# led.net
KiCad netlist of a schematic drawn in EAGLE
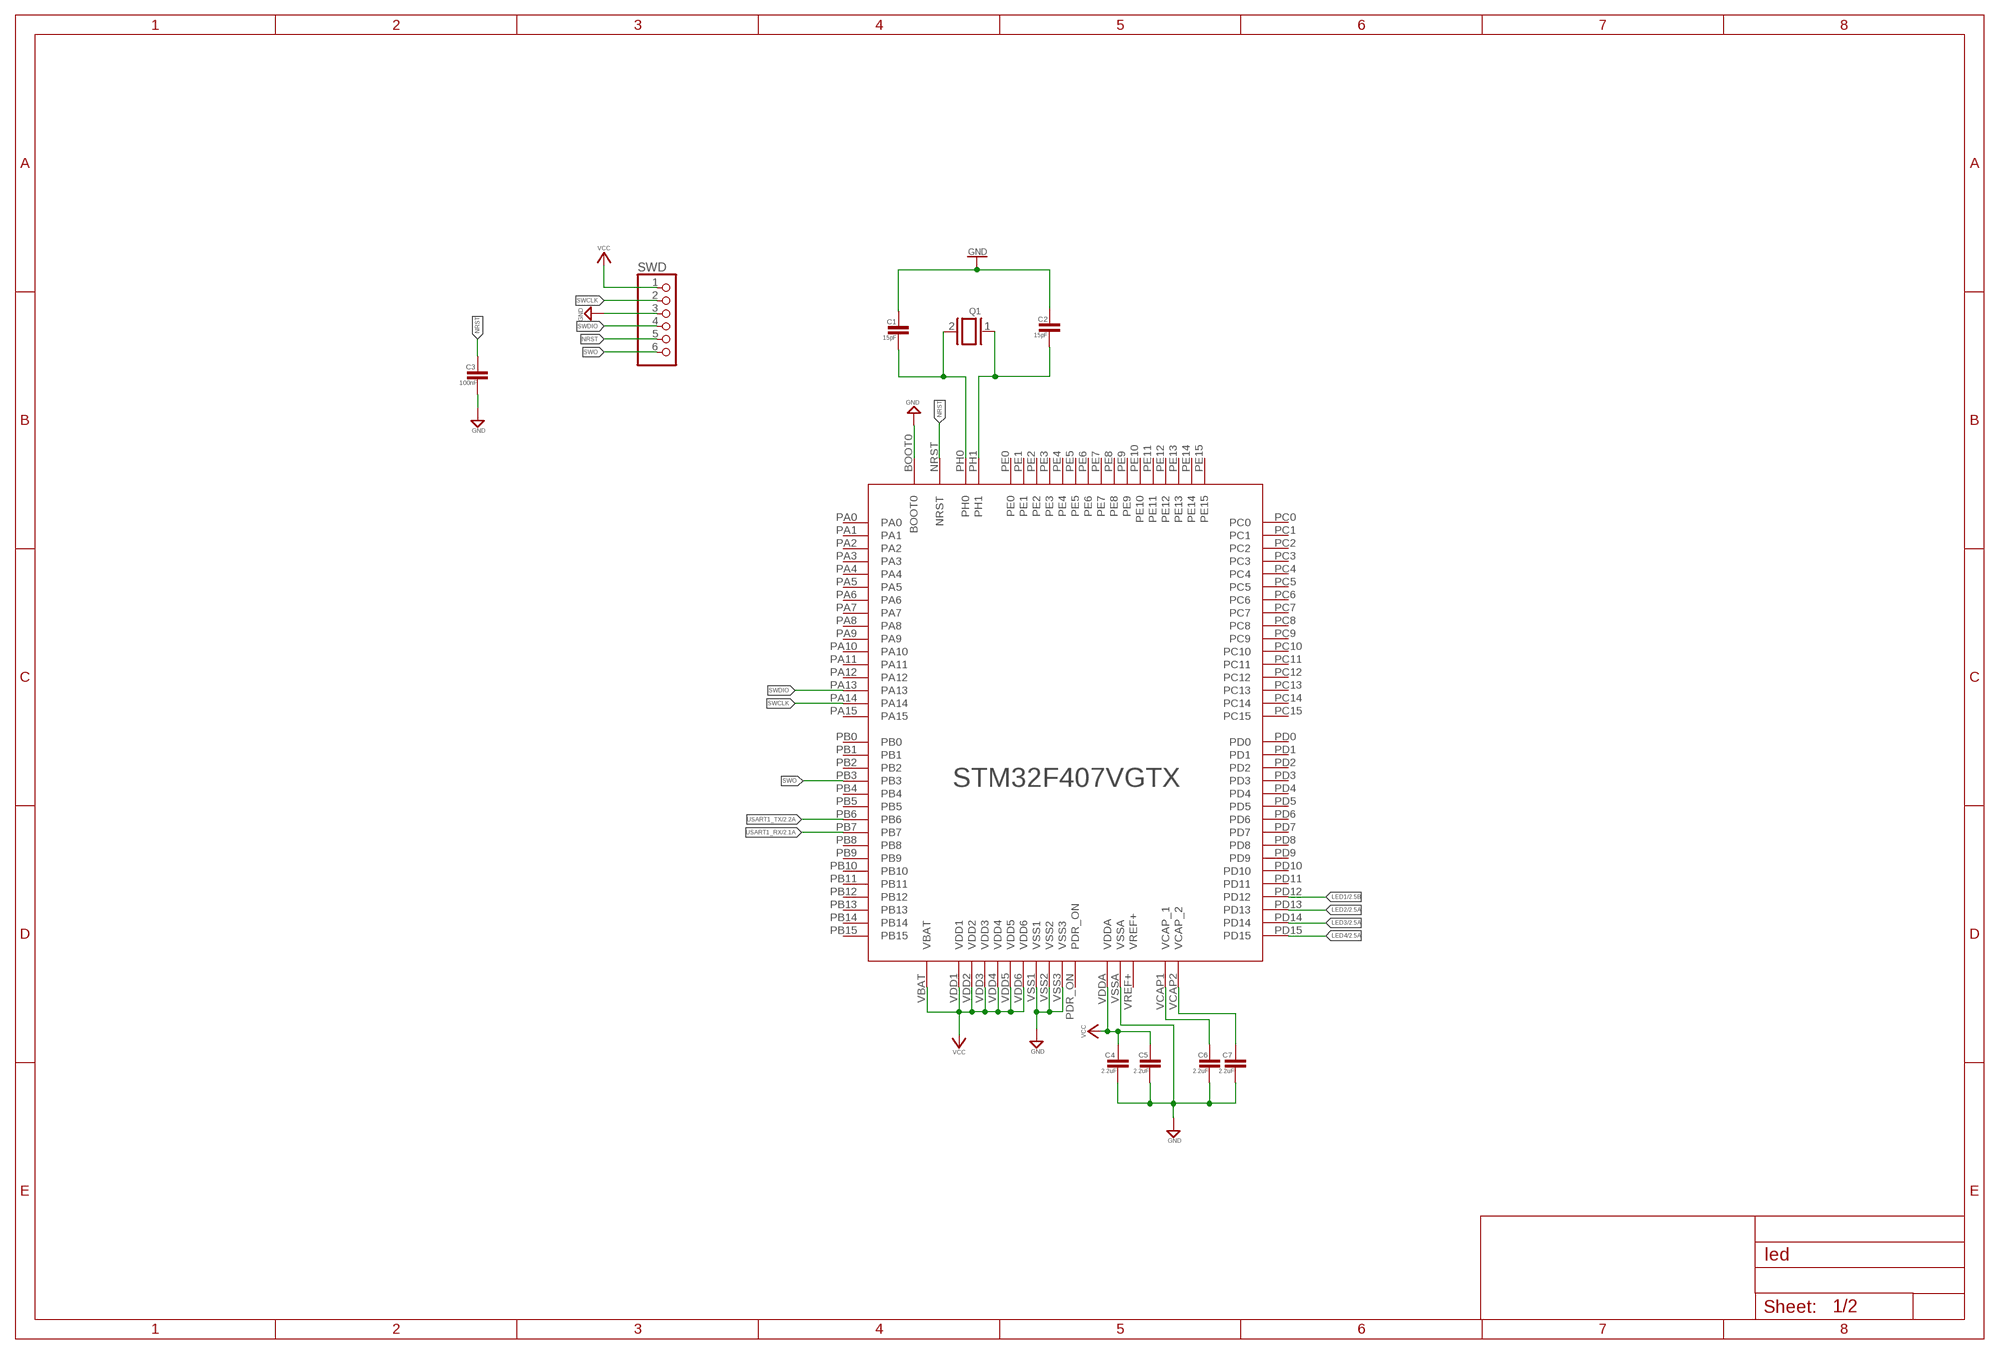
[diagram p0: schematic, sheet 1]
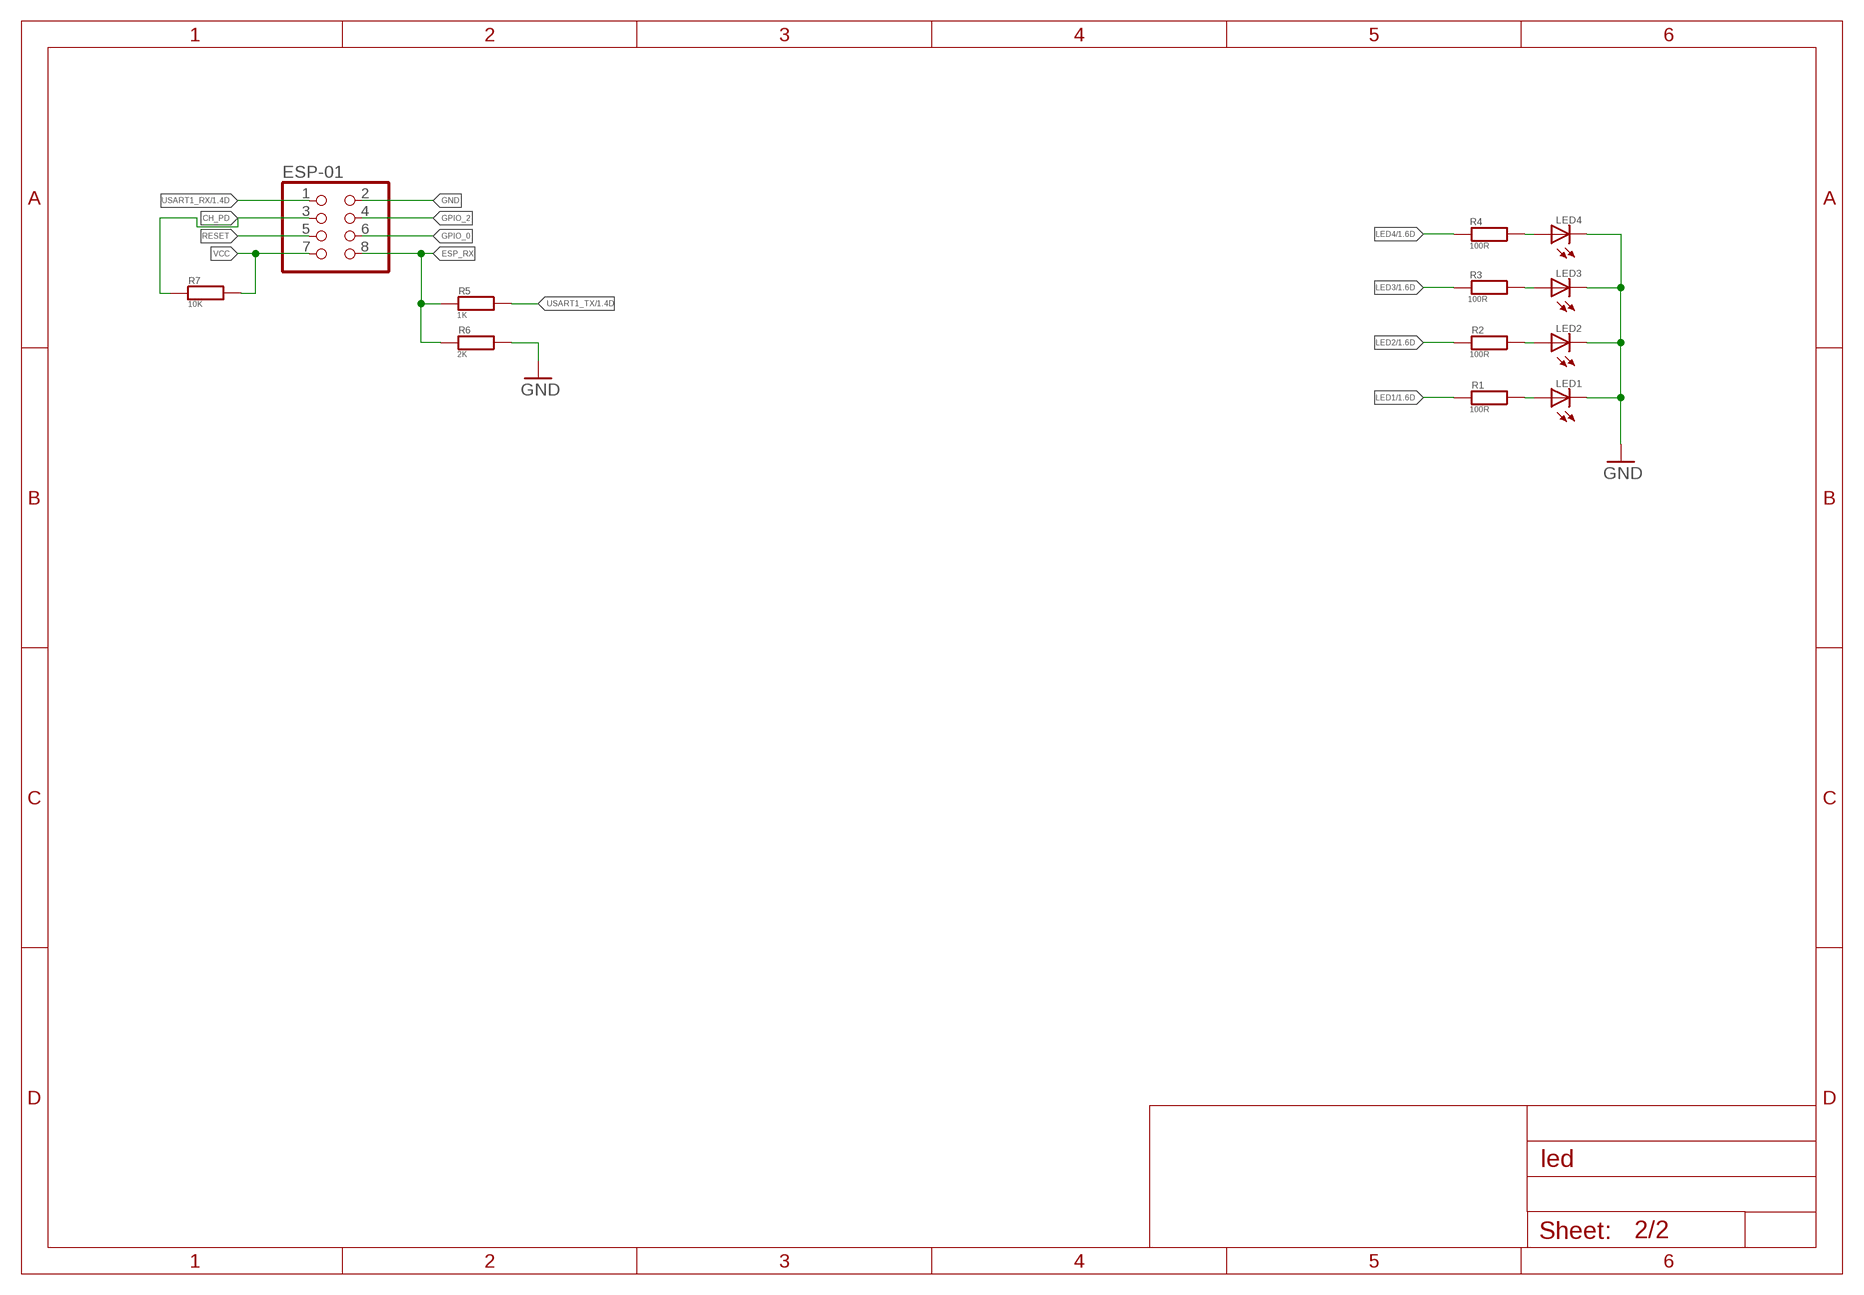
[diagram p1: schematic, sheet 2]

(export (version "E")
  (design (tool "Eeschema 10.0.6"))
  (components
    (comp (ref "C1")
      (value "15pF")
      (footprint "eagle-import:C0603")
      (libsource (lib "eagle-import") (part "C-EUC0603"))
    )
    (comp (ref "C2")
      (value "15pF")
      (footprint "eagle-import:C0603")
      (libsource (lib "eagle-import") (part "C-EUC0603"))
    )
    (comp (ref "C3")
      (value "100nF")
      (footprint "eagle-import:C0603")
      (libsource (lib "eagle-import") (part "C-EUC0603"))
    )
    (comp (ref "C4")
      (value "2.2uF")
      (footprint "eagle-import:C0603")
      (libsource (lib "eagle-import") (part "C-EUC0603"))
    )
    (comp (ref "C5")
      (value "2.2uF")
      (footprint "eagle-import:C0603")
      (libsource (lib "eagle-import") (part "C-EUC0603"))
    )
    (comp (ref "C6")
      (value "2.2uF")
      (footprint "eagle-import:C0603")
      (libsource (lib "eagle-import") (part "C-EUC0603"))
    )
    (comp (ref "C7")
      (value "2.2uF")
      (footprint "eagle-import:C0603")
      (libsource (lib "eagle-import") (part "C-EUC0603"))
    )
    (comp (ref "IC1")
      (value "STM32F407VGTx")
      (footprint "eagle-import:LQFP100")
      (libsource (lib "eagle-import") (part "STM32F4V_100PIN_GENERIC"))
    )
    (comp (ref "Q1")
      (value "XTAL/S")
      (footprint "eagle-import:QS")
      (libsource (lib "eagle-import") (part "XTAL/S"))
    )
    (comp (ref "SWD")
      (value "PINHD-1X6CB")
      (footprint "eagle-import:1X06-CLEANBIG")
      (libsource (lib "eagle-import") (part "PINHD-1X6CB"))
    )
    (comp (ref "ESP-01")
      (value "PINHD-2X4")
      (footprint "eagle-import:2X04")
      (libsource (lib "eagle-import") (part "PINHD-2X4"))
    )
    (comp (ref "LED1")
      (value "LEDCHIPLED_1206")
      (footprint "eagle-import:CHIPLED_1206")
      (libsource (lib "eagle-import") (part "LEDCHIPLED_1206"))
    )
    (comp (ref "LED2")
      (value "LEDCHIPLED_1206")
      (footprint "eagle-import:CHIPLED_1206")
      (libsource (lib "eagle-import") (part "LEDCHIPLED_1206"))
    )
    (comp (ref "LED3")
      (value "LEDCHIPLED_1206")
      (footprint "eagle-import:CHIPLED_1206")
      (libsource (lib "eagle-import") (part "LEDCHIPLED_1206"))
    )
    (comp (ref "LED4")
      (value "LEDCHIPLED_1206")
      (footprint "eagle-import:CHIPLED_1206")
      (libsource (lib "eagle-import") (part "LEDCHIPLED_1206"))
    )
    (comp (ref "R1")
      (value "100R")
      (footprint "eagle-import:R0603")
      (libsource (lib "eagle-import") (part "R-EU_R0603"))
    )
    (comp (ref "R2")
      (value "100R")
      (footprint "eagle-import:R0603")
      (libsource (lib "eagle-import") (part "R-EU_R0603"))
    )
    (comp (ref "R3")
      (value "100R")
      (footprint "eagle-import:R0603")
      (libsource (lib "eagle-import") (part "R-EU_R0603"))
    )
    (comp (ref "R4")
      (value "100R")
      (footprint "eagle-import:R0603")
      (libsource (lib "eagle-import") (part "R-EU_R0603"))
    )
    (comp (ref "R5")
      (value "1K")
      (footprint "eagle-import:R0603")
      (libsource (lib "eagle-import") (part "R-EU_R0603"))
    )
    (comp (ref "R6")
      (value "2K")
      (footprint "eagle-import:R0603")
      (libsource (lib "eagle-import") (part "R-EU_R0603"))
    )
    (comp (ref "R7")
      (value "10K")
      (footprint "eagle-import:R0603")
      (libsource (lib "eagle-import") (part "R-EU_R0603"))
    )
  )
  (nets
    (net (code "1") (name "CH_PD") (class "Default")
      (node (ref "ESP-01") (pin "3") (pinfunction "3_3") (pintype "passive"))
      (node (ref "R7") (pin "1") (pinfunction "1_1") (pintype "passive"))
    )
    (net (code "2") (name "ESP_RX") (class "Default")
      (node (ref "ESP-01") (pin "8") (pinfunction "8_8") (pintype "passive"))
      (node (ref "R5") (pin "2") (pinfunction "2_2") (pintype "passive"))
      (node (ref "R6") (pin "2") (pinfunction "2_2") (pintype "passive"))
    )
    (net (code "3") (name "GND") (class "Default")
      (node (ref "C1") (pin "1") (pinfunction "1_1") (pintype "passive"))
      (node (ref "C2") (pin "1") (pinfunction "1_1") (pintype "passive"))
      (node (ref "C3") (pin "2") (pinfunction "2_2") (pintype "passive"))
      (node (ref "C4") (pin "2") (pinfunction "2_2") (pintype "passive"))
      (node (ref "C5") (pin "2") (pinfunction "2_2") (pintype "passive"))
      (node (ref "C6") (pin "2") (pinfunction "2_2") (pintype "passive"))
      (node (ref "C7") (pin "2") (pinfunction "2_2") (pintype "passive"))
      (node (ref "ESP-01") (pin "2") (pinfunction "2_2") (pintype "passive"))
      (node (ref "IC1") (pin "BOOT0") (pinfunction "BOOT0_BOOT0") (pintype "bidirectional"))
      (node (ref "IC1") (pin "VSS1") (pinfunction "VSS1_VSS1") (pintype "bidirectional"))
      (node (ref "IC1") (pin "VSS2") (pinfunction "VSS2_VSS2") (pintype "bidirectional"))
      (node (ref "IC1") (pin "VSS3") (pinfunction "VSS3_VSS3") (pintype "bidirectional"))
      (node (ref "IC1") (pin "VSSA") (pinfunction "VSSA_VSSA") (pintype "bidirectional"))
      (node (ref "LED1") (pin "C") (pinfunction "C_C") (pintype "passive"))
      (node (ref "LED2") (pin "C") (pinfunction "C_C") (pintype "passive"))
      (node (ref "LED3") (pin "C") (pinfunction "C_C") (pintype "passive"))
      (node (ref "LED4") (pin "C") (pinfunction "C_C") (pintype "passive"))
      (node (ref "R6") (pin "1") (pinfunction "1_1") (pintype "passive"))
      (node (ref "SWD") (pin "3") (pinfunction "3_3") (pintype "passive"))
    )
    (net (code "4") (name "GPIO_0") (class "Default")
      (node (ref "ESP-01") (pin "6") (pinfunction "6_6") (pintype "passive"))
    )
    (net (code "5") (name "GPIO_2") (class "Default")
      (node (ref "ESP-01") (pin "4") (pinfunction "4_4") (pintype "passive"))
    )
    (net (code "6") (name "LED1") (class "Default")
      (node (ref "IC1") (pin "PD12") (pinfunction "PD12_PD12") (pintype "bidirectional"))
      (node (ref "R1") (pin "2") (pinfunction "2_2") (pintype "passive"))
    )
    (net (code "7") (name "LED2") (class "Default")
      (node (ref "IC1") (pin "PD13") (pinfunction "PD13_PD13") (pintype "bidirectional"))
      (node (ref "R2") (pin "2") (pinfunction "2_2") (pintype "passive"))
    )
    (net (code "8") (name "LED3") (class "Default")
      (node (ref "IC1") (pin "PD14") (pinfunction "PD14_PD14") (pintype "bidirectional"))
      (node (ref "R3") (pin "2") (pinfunction "2_2") (pintype "passive"))
    )
    (net (code "9") (name "LED4") (class "Default")
      (node (ref "IC1") (pin "PD15") (pinfunction "PD15_PD15") (pintype "bidirectional"))
      (node (ref "R4") (pin "2") (pinfunction "2_2") (pintype "passive"))
    )
    (net (code "10") (name "NRST") (class "Default")
      (node (ref "C3") (pin "1") (pinfunction "1_1") (pintype "passive"))
      (node (ref "IC1") (pin "NRST") (pinfunction "NRST_NRST") (pintype "bidirectional"))
      (node (ref "SWD") (pin "5") (pinfunction "5_5") (pintype "passive"))
    )
    (net (code "11") (name "Net-(C1-Pad2)") (class "Default")
      (node (ref "C1") (pin "2") (pinfunction "2_2") (pintype "passive"))
      (node (ref "IC1") (pin "PH0") (pinfunction "PH0_PH0") (pintype "bidirectional"))
      (node (ref "Q1") (pin "2") (pinfunction "2_2") (pintype "passive"))
    )
    (net (code "12") (name "Net-(C2-Pad2)") (class "Default")
      (node (ref "C2") (pin "2") (pinfunction "2_2") (pintype "passive"))
      (node (ref "IC1") (pin "PH1") (pinfunction "PH1_PH1") (pintype "bidirectional"))
      (node (ref "Q1") (pin "1") (pinfunction "1_1") (pintype "passive"))
    )
    (net (code "13") (name "Net-(IC1-VCAP_1)") (class "Default")
      (node (ref "C6") (pin "1") (pinfunction "1_1") (pintype "passive"))
      (node (ref "IC1") (pin "VCAP1") (pinfunction "VCAP_1_VCAP1") (pintype "bidirectional"))
    )
    (net (code "14") (name "Net-(IC1-VCAP_2)") (class "Default")
      (node (ref "C7") (pin "1") (pinfunction "1_1") (pintype "passive"))
      (node (ref "IC1") (pin "VCAP2") (pinfunction "VCAP_2_VCAP2") (pintype "bidirectional"))
    )
    (net (code "15") (name "Net-(LED1-PadA)") (class "Default")
      (node (ref "LED1") (pin "A") (pinfunction "A_A") (pintype "passive"))
      (node (ref "R1") (pin "1") (pinfunction "1_1") (pintype "passive"))
    )
    (net (code "16") (name "Net-(LED2-PadA)") (class "Default")
      (node (ref "LED2") (pin "A") (pinfunction "A_A") (pintype "passive"))
      (node (ref "R2") (pin "1") (pinfunction "1_1") (pintype "passive"))
    )
    (net (code "17") (name "Net-(LED3-PadA)") (class "Default")
      (node (ref "LED3") (pin "A") (pinfunction "A_A") (pintype "passive"))
      (node (ref "R3") (pin "1") (pinfunction "1_1") (pintype "passive"))
    )
    (net (code "18") (name "Net-(LED4-PadA)") (class "Default")
      (node (ref "LED4") (pin "A") (pinfunction "A_A") (pintype "passive"))
      (node (ref "R4") (pin "1") (pinfunction "1_1") (pintype "passive"))
    )
    (net (code "19") (name "RESET") (class "Default")
      (node (ref "ESP-01") (pin "5") (pinfunction "5_5") (pintype "passive"))
    )
    (net (code "20") (name "SWCLK") (class "Default")
      (node (ref "IC1") (pin "PA14") (pinfunction "PA14_PA14") (pintype "bidirectional"))
      (node (ref "SWD") (pin "2") (pinfunction "2_2") (pintype "passive"))
    )
    (net (code "21") (name "SWDIO") (class "Default")
      (node (ref "IC1") (pin "PA13") (pinfunction "PA13_PA13") (pintype "bidirectional"))
      (node (ref "SWD") (pin "4") (pinfunction "4_4") (pintype "passive"))
    )
    (net (code "22") (name "SWO") (class "Default")
      (node (ref "IC1") (pin "PB3") (pinfunction "PB3_PB3") (pintype "bidirectional"))
      (node (ref "SWD") (pin "6") (pinfunction "6_6") (pintype "passive"))
    )
    (net (code "23") (name "USART1_RX") (class "Default")
      (node (ref "ESP-01") (pin "1") (pinfunction "1_1") (pintype "passive"))
      (node (ref "IC1") (pin "PB7") (pinfunction "PB7_PB7") (pintype "bidirectional"))
    )
    (net (code "24") (name "USART1_TX") (class "Default")
      (node (ref "IC1") (pin "PB6") (pinfunction "PB6_PB6") (pintype "bidirectional"))
      (node (ref "R5") (pin "1") (pinfunction "1_1") (pintype "passive"))
    )
    (net (code "25") (name "VCC") (class "Default")
      (node (ref "C4") (pin "1") (pinfunction "1_1") (pintype "passive"))
      (node (ref "C5") (pin "1") (pinfunction "1_1") (pintype "passive"))
      (node (ref "ESP-01") (pin "7") (pinfunction "7_7") (pintype "passive"))
      (node (ref "IC1") (pin "VBAT") (pinfunction "VBAT_VBAT") (pintype "bidirectional"))
      (node (ref "IC1") (pin "VDD1") (pinfunction "VDD1_VDD1") (pintype "bidirectional"))
      (node (ref "IC1") (pin "VDD2") (pinfunction "VDD2_VDD2") (pintype "bidirectional"))
      (node (ref "IC1") (pin "VDD3") (pinfunction "VDD3_VDD3") (pintype "bidirectional"))
      (node (ref "IC1") (pin "VDD4") (pinfunction "VDD4_VDD4") (pintype "bidirectional"))
      (node (ref "IC1") (pin "VDD5") (pinfunction "VDD5_VDD5") (pintype "bidirectional"))
      (node (ref "IC1") (pin "VDD6") (pinfunction "VDD6_VDD6") (pintype "bidirectional"))
      (node (ref "IC1") (pin "VDDA") (pinfunction "VDDA_VDDA") (pintype "bidirectional"))
      (node (ref "R7") (pin "2") (pinfunction "2_2") (pintype "passive"))
      (node (ref "SWD") (pin "1") (pinfunction "1_1") (pintype "passive"))
    )
    (net (code "26") (name "unconnected-(IC1-PadPA0)") (class "Default")
      (node (ref "IC1") (pin "PA0") (pinfunction "PA0_PA0") (pintype "bidirectional"))
    )
    (net (code "27") (name "unconnected-(IC1-PadPA1)") (class "Default")
      (node (ref "IC1") (pin "PA1") (pinfunction "PA1_PA1") (pintype "bidirectional"))
    )
    (net (code "28") (name "unconnected-(IC1-PadPA2)") (class "Default")
      (node (ref "IC1") (pin "PA2") (pinfunction "PA2_PA2") (pintype "bidirectional"))
    )
    (net (code "29") (name "unconnected-(IC1-PadPA3)") (class "Default")
      (node (ref "IC1") (pin "PA3") (pinfunction "PA3_PA3") (pintype "bidirectional"))
    )
    (net (code "30") (name "unconnected-(IC1-PadPA4)") (class "Default")
      (node (ref "IC1") (pin "PA4") (pinfunction "PA4_PA4") (pintype "bidirectional"))
    )
    (net (code "31") (name "unconnected-(IC1-PadPA5)") (class "Default")
      (node (ref "IC1") (pin "PA5") (pinfunction "PA5_PA5") (pintype "bidirectional"))
    )
    (net (code "32") (name "unconnected-(IC1-PadPA6)") (class "Default")
      (node (ref "IC1") (pin "PA6") (pinfunction "PA6_PA6") (pintype "bidirectional"))
    )
    (net (code "33") (name "unconnected-(IC1-PadPA7)") (class "Default")
      (node (ref "IC1") (pin "PA7") (pinfunction "PA7_PA7") (pintype "bidirectional"))
    )
    (net (code "34") (name "unconnected-(IC1-PadPA8)") (class "Default")
      (node (ref "IC1") (pin "PA8") (pinfunction "PA8_PA8") (pintype "bidirectional"))
    )
    (net (code "35") (name "unconnected-(IC1-PadPA9)") (class "Default")
      (node (ref "IC1") (pin "PA9") (pinfunction "PA9_PA9") (pintype "bidirectional"))
    )
    (net (code "36") (name "unconnected-(IC1-PadPA10)") (class "Default")
      (node (ref "IC1") (pin "PA10") (pinfunction "PA10_PA10") (pintype "bidirectional"))
    )
    (net (code "37") (name "unconnected-(IC1-PadPA11)") (class "Default")
      (node (ref "IC1") (pin "PA11") (pinfunction "PA11_PA11") (pintype "bidirectional"))
    )
    (net (code "38") (name "unconnected-(IC1-PadPA12)") (class "Default")
      (node (ref "IC1") (pin "PA12") (pinfunction "PA12_PA12") (pintype "bidirectional"))
    )
    (net (code "39") (name "unconnected-(IC1-PadPA15)") (class "Default")
      (node (ref "IC1") (pin "PA15") (pinfunction "PA15_PA15") (pintype "bidirectional"))
    )
    (net (code "40") (name "unconnected-(IC1-PadPB0)") (class "Default")
      (node (ref "IC1") (pin "PB0") (pinfunction "PB0_PB0") (pintype "bidirectional"))
    )
    (net (code "41") (name "unconnected-(IC1-PadPB1)") (class "Default")
      (node (ref "IC1") (pin "PB1") (pinfunction "PB1_PB1") (pintype "bidirectional"))
    )
    (net (code "42") (name "unconnected-(IC1-PadPB2)") (class "Default")
      (node (ref "IC1") (pin "PB2") (pinfunction "PB2_PB2") (pintype "bidirectional"))
    )
    (net (code "43") (name "unconnected-(IC1-PadPB4)") (class "Default")
      (node (ref "IC1") (pin "PB4") (pinfunction "PB4_PB4") (pintype "bidirectional"))
    )
    (net (code "44") (name "unconnected-(IC1-PadPB5)") (class "Default")
      (node (ref "IC1") (pin "PB5") (pinfunction "PB5_PB5") (pintype "bidirectional"))
    )
    (net (code "45") (name "unconnected-(IC1-PadPB8)") (class "Default")
      (node (ref "IC1") (pin "PB8") (pinfunction "PB8_PB8") (pintype "bidirectional"))
    )
    (net (code "46") (name "unconnected-(IC1-PadPB9)") (class "Default")
      (node (ref "IC1") (pin "PB9") (pinfunction "PB9_PB9") (pintype "bidirectional"))
    )
    (net (code "47") (name "unconnected-(IC1-PadPB10)") (class "Default")
      (node (ref "IC1") (pin "PB10") (pinfunction "PB10_PB10") (pintype "bidirectional"))
    )
    (net (code "48") (name "unconnected-(IC1-PadPB11)") (class "Default")
      (node (ref "IC1") (pin "PB11") (pinfunction "PB11_PB11") (pintype "bidirectional"))
    )
    (net (code "49") (name "unconnected-(IC1-PadPB12)") (class "Default")
      (node (ref "IC1") (pin "PB12") (pinfunction "PB12_PB12") (pintype "bidirectional"))
    )
    (net (code "50") (name "unconnected-(IC1-PadPB13)") (class "Default")
      (node (ref "IC1") (pin "PB13") (pinfunction "PB13_PB13") (pintype "bidirectional"))
    )
    (net (code "51") (name "unconnected-(IC1-PadPB14)") (class "Default")
      (node (ref "IC1") (pin "PB14") (pinfunction "PB14_PB14") (pintype "bidirectional"))
    )
    (net (code "52") (name "unconnected-(IC1-PadPB15)") (class "Default")
      (node (ref "IC1") (pin "PB15") (pinfunction "PB15_PB15") (pintype "bidirectional"))
    )
    (net (code "53") (name "unconnected-(IC1-PadPC0)") (class "Default")
      (node (ref "IC1") (pin "PC0") (pinfunction "PC0_PC0") (pintype "bidirectional"))
    )
    (net (code "54") (name "unconnected-(IC1-PadPC1)") (class "Default")
      (node (ref "IC1") (pin "PC1") (pinfunction "PC1_PC1") (pintype "bidirectional"))
    )
    (net (code "55") (name "unconnected-(IC1-PadPC2)") (class "Default")
      (node (ref "IC1") (pin "PC2") (pinfunction "PC2_PC2") (pintype "bidirectional"))
    )
    (net (code "56") (name "unconnected-(IC1-PadPC3)") (class "Default")
      (node (ref "IC1") (pin "PC3") (pinfunction "PC3_PC3") (pintype "bidirectional"))
    )
    (net (code "57") (name "unconnected-(IC1-PadPC4)") (class "Default")
      (node (ref "IC1") (pin "PC4") (pinfunction "PC4_PC4") (pintype "bidirectional"))
    )
    (net (code "58") (name "unconnected-(IC1-PadPC5)") (class "Default")
      (node (ref "IC1") (pin "PC5") (pinfunction "PC5_PC5") (pintype "bidirectional"))
    )
    (net (code "59") (name "unconnected-(IC1-PadPC6)") (class "Default")
      (node (ref "IC1") (pin "PC6") (pinfunction "PC6_PC6") (pintype "bidirectional"))
    )
    (net (code "60") (name "unconnected-(IC1-PadPC7)") (class "Default")
      (node (ref "IC1") (pin "PC7") (pinfunction "PC7_PC7") (pintype "bidirectional"))
    )
    (net (code "61") (name "unconnected-(IC1-PadPC8)") (class "Default")
      (node (ref "IC1") (pin "PC8") (pinfunction "PC8_PC8") (pintype "bidirectional"))
    )
    (net (code "62") (name "unconnected-(IC1-PadPC9)") (class "Default")
      (node (ref "IC1") (pin "PC9") (pinfunction "PC9_PC9") (pintype "bidirectional"))
    )
    (net (code "63") (name "unconnected-(IC1-PadPC10)") (class "Default")
      (node (ref "IC1") (pin "PC10") (pinfunction "PC10_PC10") (pintype "bidirectional"))
    )
    (net (code "64") (name "unconnected-(IC1-PadPC11)") (class "Default")
      (node (ref "IC1") (pin "PC11") (pinfunction "PC11_PC11") (pintype "bidirectional"))
    )
    (net (code "65") (name "unconnected-(IC1-PadPC12)") (class "Default")
      (node (ref "IC1") (pin "PC12") (pinfunction "PC12_PC12") (pintype "bidirectional"))
    )
    (net (code "66") (name "unconnected-(IC1-PadPC13)") (class "Default")
      (node (ref "IC1") (pin "PC13") (pinfunction "PC13_PC13") (pintype "bidirectional"))
    )
    (net (code "67") (name "unconnected-(IC1-PadPC14)") (class "Default")
      (node (ref "IC1") (pin "PC14") (pinfunction "PC14_PC14") (pintype "bidirectional"))
    )
    (net (code "68") (name "unconnected-(IC1-PadPC15)") (class "Default")
      (node (ref "IC1") (pin "PC15") (pinfunction "PC15_PC15") (pintype "bidirectional"))
    )
    (net (code "69") (name "unconnected-(IC1-PadPD0)") (class "Default")
      (node (ref "IC1") (pin "PD0") (pinfunction "PD0_PD0") (pintype "bidirectional"))
    )
    (net (code "70") (name "unconnected-(IC1-PadPD1)") (class "Default")
      (node (ref "IC1") (pin "PD1") (pinfunction "PD1_PD1") (pintype "bidirectional"))
    )
    (net (code "71") (name "unconnected-(IC1-PadPD2)") (class "Default")
      (node (ref "IC1") (pin "PD2") (pinfunction "PD2_PD2") (pintype "bidirectional"))
    )
    (net (code "72") (name "unconnected-(IC1-PadPD3)") (class "Default")
      (node (ref "IC1") (pin "PD3") (pinfunction "PD3_PD3") (pintype "bidirectional"))
    )
    (net (code "73") (name "unconnected-(IC1-PadPD4)") (class "Default")
      (node (ref "IC1") (pin "PD4") (pinfunction "PD4_PD4") (pintype "bidirectional"))
    )
    (net (code "74") (name "unconnected-(IC1-PadPD5)") (class "Default")
      (node (ref "IC1") (pin "PD5") (pinfunction "PD5_PD5") (pintype "bidirectional"))
    )
    (net (code "75") (name "unconnected-(IC1-PadPD6)") (class "Default")
      (node (ref "IC1") (pin "PD6") (pinfunction "PD6_PD6") (pintype "bidirectional"))
    )
    (net (code "76") (name "unconnected-(IC1-PadPD7)") (class "Default")
      (node (ref "IC1") (pin "PD7") (pinfunction "PD7_PD7") (pintype "bidirectional"))
    )
    (net (code "77") (name "unconnected-(IC1-PadPD8)") (class "Default")
      (node (ref "IC1") (pin "PD8") (pinfunction "PD8_PD8") (pintype "bidirectional"))
    )
    (net (code "78") (name "unconnected-(IC1-PadPD9)") (class "Default")
      (node (ref "IC1") (pin "PD9") (pinfunction "PD9_PD9") (pintype "bidirectional"))
    )
    (net (code "79") (name "unconnected-(IC1-PadPD10)") (class "Default")
      (node (ref "IC1") (pin "PD10") (pinfunction "PD10_PD10") (pintype "bidirectional"))
    )
    (net (code "80") (name "unconnected-(IC1-PadPD11)") (class "Default")
      (node (ref "IC1") (pin "PD11") (pinfunction "PD11_PD11") (pintype "bidirectional"))
    )
    (net (code "81") (name "unconnected-(IC1-PadPDR_ON)") (class "Default")
      (node (ref "IC1") (pin "PDR_ON") (pinfunction "PDR_ON_PDR_ON") (pintype "bidirectional"))
    )
    (net (code "82") (name "unconnected-(IC1-PadPE0)") (class "Default")
      (node (ref "IC1") (pin "PE0") (pinfunction "PE0_PE0") (pintype "bidirectional"))
    )
    (net (code "83") (name "unconnected-(IC1-PadPE1)") (class "Default")
      (node (ref "IC1") (pin "PE1") (pinfunction "PE1_PE1") (pintype "bidirectional"))
    )
    (net (code "84") (name "unconnected-(IC1-PadPE2)") (class "Default")
      (node (ref "IC1") (pin "PE2") (pinfunction "PE2_PE2") (pintype "bidirectional"))
    )
    (net (code "85") (name "unconnected-(IC1-PadPE3)") (class "Default")
      (node (ref "IC1") (pin "PE3") (pinfunction "PE3_PE3") (pintype "bidirectional"))
    )
    (net (code "86") (name "unconnected-(IC1-PadPE4)") (class "Default")
      (node (ref "IC1") (pin "PE4") (pinfunction "PE4_PE4") (pintype "bidirectional"))
    )
    (net (code "87") (name "unconnected-(IC1-PadPE5)") (class "Default")
      (node (ref "IC1") (pin "PE5") (pinfunction "PE5_PE5") (pintype "bidirectional"))
    )
    (net (code "88") (name "unconnected-(IC1-PadPE6)") (class "Default")
      (node (ref "IC1") (pin "PE6") (pinfunction "PE6_PE6") (pintype "bidirectional"))
    )
    (net (code "89") (name "unconnected-(IC1-PadPE7)") (class "Default")
      (node (ref "IC1") (pin "PE7") (pinfunction "PE7_PE7") (pintype "bidirectional"))
    )
    (net (code "90") (name "unconnected-(IC1-PadPE8)") (class "Default")
      (node (ref "IC1") (pin "PE8") (pinfunction "PE8_PE8") (pintype "bidirectional"))
    )
    (net (code "91") (name "unconnected-(IC1-PadPE9)") (class "Default")
      (node (ref "IC1") (pin "PE9") (pinfunction "PE9_PE9") (pintype "bidirectional"))
    )
    (net (code "92") (name "unconnected-(IC1-PadPE10)") (class "Default")
      (node (ref "IC1") (pin "PE10") (pinfunction "PE10_PE10") (pintype "bidirectional"))
    )
    (net (code "93") (name "unconnected-(IC1-PadPE11)") (class "Default")
      (node (ref "IC1") (pin "PE11") (pinfunction "PE11_PE11") (pintype "bidirectional"))
    )
    (net (code "94") (name "unconnected-(IC1-PadPE12)") (class "Default")
      (node (ref "IC1") (pin "PE12") (pinfunction "PE12_PE12") (pintype "bidirectional"))
    )
    (net (code "95") (name "unconnected-(IC1-PadPE13)") (class "Default")
      (node (ref "IC1") (pin "PE13") (pinfunction "PE13_PE13") (pintype "bidirectional"))
    )
    (net (code "96") (name "unconnected-(IC1-PadPE14)") (class "Default")
      (node (ref "IC1") (pin "PE14") (pinfunction "PE14_PE14") (pintype "bidirectional"))
    )
    (net (code "97") (name "unconnected-(IC1-PadPE15)") (class "Default")
      (node (ref "IC1") (pin "PE15") (pinfunction "PE15_PE15") (pintype "bidirectional"))
    )
    (net (code "98") (name "unconnected-(IC1-PadVREF+)") (class "Default")
      (node (ref "IC1") (pin "VREF+") (pinfunction "VREF+_VREF+") (pintype "bidirectional"))
    )
  )
)
